# FTDI_Basic-v21-5V.net
KiCad netlist of a schematic drawn in EAGLE
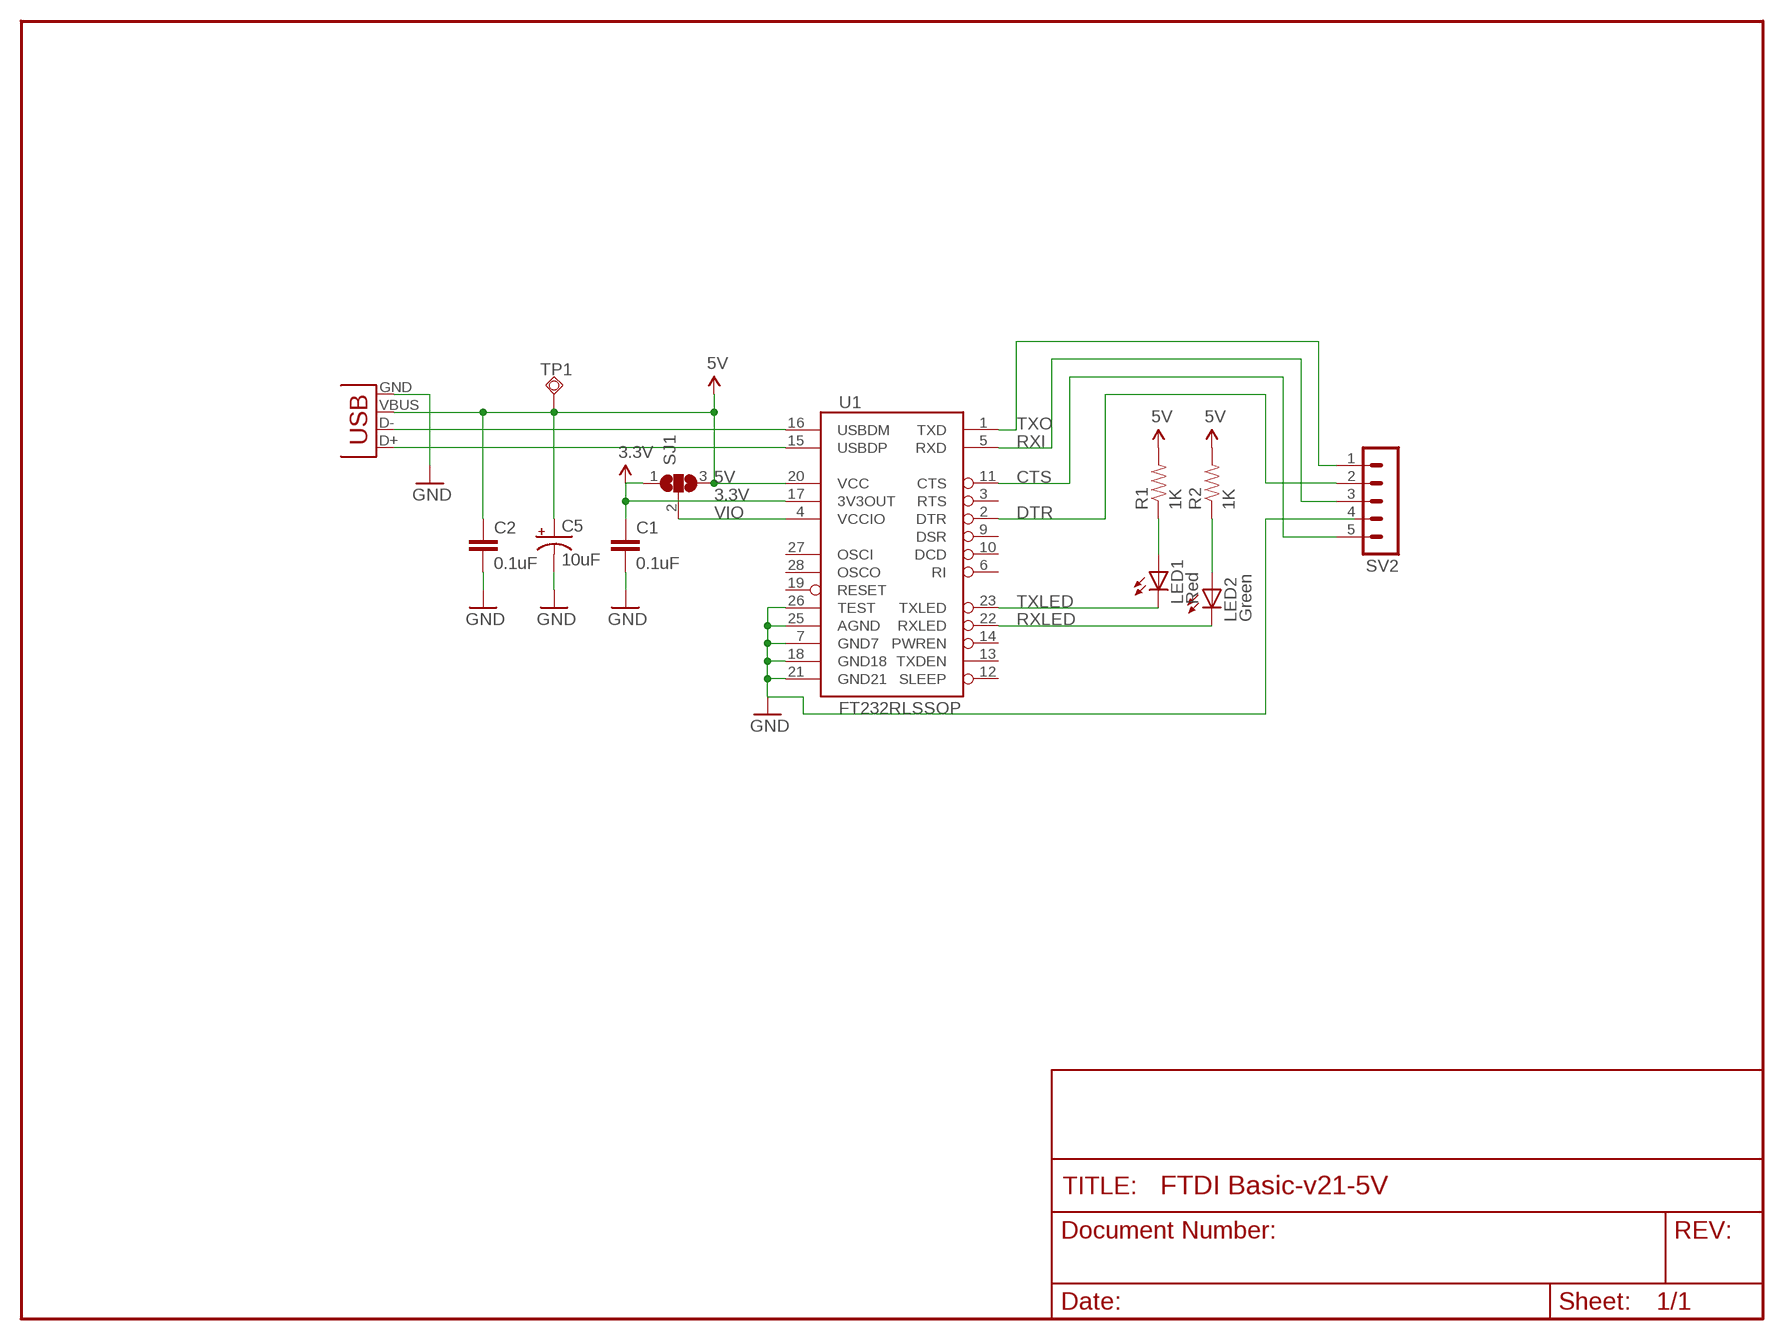
[diagram p0: schematic, sheet 1]

(export (version "E")
  (design (tool "Eeschema 10.0.6"))
  (components
    (comp (ref "C1")
      (value "0.1uF")
      (footprint "eagle-import:0402-CAP")
      (libsource (lib "eagle-import") (part "CAP0402-CAP"))
    )
    (comp (ref "C2")
      (value "0.1uF")
      (footprint "eagle-import:0402-CAP")
      (libsource (lib "eagle-import") (part "CAP0402-CAP"))
    )
    (comp (ref "C5")
      (value "10uF")
      (footprint "eagle-import:EIA3216")
      (libsource (lib "eagle-import") (part "CAP_POL1206"))
    )
    (comp (ref "LED1")
      (value "Red")
      (footprint "eagle-import:LED-0603")
      (libsource (lib "eagle-import") (part "LED0603"))
    )
    (comp (ref "LED2")
      (value "Green")
      (footprint "eagle-import:LED-0603")
      (libsource (lib "eagle-import") (part "LED0603"))
    )
    (comp (ref "R1")
      (value "1K")
      (footprint "eagle-import:0402-RES")
      (libsource (lib "eagle-import") (part "RESISTOR0402-RES"))
    )
    (comp (ref "R2")
      (value "1K")
      (footprint "eagle-import:0402-RES")
      (libsource (lib "eagle-import") (part "RESISTOR0402-RES"))
    )
    (comp (ref "SJ1")
      (value "SJ2W")
      (footprint "eagle-import:SJ_2")
      (libsource (lib "eagle-import") (part "SJ2W"))
    )
    (comp (ref "SV2")
      (value "MA05-1")
      (footprint "eagle-import:MA05-1")
      (libsource (lib "eagle-import") (part "MA05-1"))
    )
    (comp (ref "TP1")
      (value "TPSQPAD1-13")
      (footprint "eagle-import:P1-13")
      (libsource (lib "eagle-import") (part "TPSQPAD1-13"))
    )
    (comp (ref "U1")
      (value "FT232RLSSOP")
      (footprint "eagle-import:SSOP28DB")
      (libsource (lib "eagle-import") (part "FT232RLSSOP"))
    )
    (comp (ref "X2")
      (value "USBPTH")
      (footprint "eagle-import:USB-B-PTH")
      (libsource (lib "eagle-import") (part "USBPTH"))
    )
  )
  (nets
    (net (code "1") (name "/CTS") (class "Default")
      (node (ref "SV2") (pin "5") (pinfunction "5_5") (pintype "passive"))
      (node (ref "U1") (pin "11") (pinfunction "CTS_11") (pintype "input"))
    )
    (net (code "2") (name "/DTR") (class "Default")
      (node (ref "SV2") (pin "2") (pinfunction "2_2") (pintype "passive"))
      (node (ref "U1") (pin "2") (pinfunction "DTR_2") (pintype "output"))
    )
    (net (code "3") (name "/RXI") (class "Default")
      (node (ref "SV2") (pin "3") (pinfunction "3_3") (pintype "passive"))
      (node (ref "U1") (pin "5") (pinfunction "RXD_5") (pintype "input"))
    )
    (net (code "4") (name "/RXLED") (class "Default")
      (node (ref "LED2") (pin "C") (pinfunction "C_C") (pintype "passive"))
      (node (ref "U1") (pin "22") (pinfunction "RXLED_22") (pintype "input"))
    )
    (net (code "5") (name "/TXLED") (class "Default")
      (node (ref "LED1") (pin "C") (pinfunction "C_C") (pintype "passive"))
      (node (ref "U1") (pin "23") (pinfunction "TXLED_23") (pintype "input"))
    )
    (net (code "6") (name "/TXO") (class "Default")
      (node (ref "SV2") (pin "1") (pinfunction "1_1") (pintype "passive"))
      (node (ref "U1") (pin "1") (pinfunction "TXD_1") (pintype "output"))
    )
    (net (code "7") (name "/VIO") (class "Default")
      (node (ref "SJ1") (pin "2") (pinfunction "2_2") (pintype "passive"))
      (node (ref "U1") (pin "4") (pinfunction "VCCIO_4") (pintype "power_in"))
    )
    (net (code "8") (name "3.3V") (class "Default")
      (node (ref "C1") (pin "1") (pinfunction "1_1") (pintype "passive"))
      (node (ref "SJ1") (pin "1") (pinfunction "1_1") (pintype "passive"))
      (node (ref "U1") (pin "17") (pinfunction "3V3OUT_17") (pintype "output"))
    )
    (net (code "9") (name "5V") (class "Default")
      (node (ref "C2") (pin "1") (pinfunction "1_1") (pintype "passive"))
      (node (ref "C5") (pin "A") (pinfunction "+_A") (pintype "passive"))
      (node (ref "R1") (pin "2") (pinfunction "2_2") (pintype "passive"))
      (node (ref "R2") (pin "2") (pinfunction "2_2") (pintype "passive"))
      (node (ref "SJ1") (pin "3") (pinfunction "3_3") (pintype "passive"))
      (node (ref "TP1") (pin "TP") (pinfunction "TP_TP") (pintype "input"))
      (node (ref "U1") (pin "20") (pinfunction "VCC_20") (pintype "power_in"))
      (node (ref "X2") (pin "VBUS") (pinfunction "VBUS_VBUS") (pintype "bidirectional"))
    )
    (net (code "10") (name "GND") (class "Default")
      (node (ref "C1") (pin "2") (pinfunction "2_2") (pintype "passive"))
      (node (ref "C2") (pin "2") (pinfunction "2_2") (pintype "passive"))
      (node (ref "C5") (pin "C") (pinfunction "-_C") (pintype "passive"))
      (node (ref "SV2") (pin "4") (pinfunction "4_4") (pintype "passive"))
      (node (ref "U1") (pin "18") (pinfunction "GND18_18") (pintype "power_in"))
      (node (ref "U1") (pin "21") (pinfunction "GND21_21") (pintype "power_in"))
      (node (ref "U1") (pin "25") (pinfunction "AGND_25") (pintype "power_in"))
      (node (ref "U1") (pin "26") (pinfunction "TEST_26") (pintype "input"))
      (node (ref "U1") (pin "7") (pinfunction "GND7_7") (pintype "power_in"))
      (node (ref "X2") (pin "GND") (pinfunction "GND_GND") (pintype "bidirectional"))
    )
    (net (code "11") (name "Net-(LED1-PadA)") (class "Default")
      (node (ref "LED1") (pin "A") (pinfunction "A_A") (pintype "passive"))
      (node (ref "R1") (pin "1") (pinfunction "1_1") (pintype "passive"))
    )
    (net (code "12") (name "Net-(LED2-PadA)") (class "Default")
      (node (ref "LED2") (pin "A") (pinfunction "A_A") (pintype "passive"))
      (node (ref "R2") (pin "1") (pinfunction "1_1") (pintype "passive"))
    )
    (net (code "13") (name "Net-(U1-USBDM)") (class "Default")
      (node (ref "U1") (pin "16") (pinfunction "USBDM_16") (pintype "bidirectional"))
      (node (ref "X2") (pin "D-") (pinfunction "D-_D-") (pintype "bidirectional"))
    )
    (net (code "14") (name "Net-(U1-USBDP)") (class "Default")
      (node (ref "U1") (pin "15") (pinfunction "USBDP_15") (pintype "bidirectional"))
      (node (ref "X2") (pin "D+") (pinfunction "D+_D+") (pintype "bidirectional"))
    )
    (net (code "15") (name "unconnected-(U1-DCD-Pad10)") (class "Default")
      (node (ref "U1") (pin "10") (pinfunction "DCD_10") (pintype "input"))
    )
    (net (code "16") (name "unconnected-(U1-DSR-Pad9)") (class "Default")
      (node (ref "U1") (pin "9") (pinfunction "DSR_9") (pintype "input"))
    )
    (net (code "17") (name "unconnected-(U1-OSCI-Pad27)") (class "Default")
      (node (ref "U1") (pin "27") (pinfunction "OSCI_27") (pintype "input"))
    )
    (net (code "18") (name "unconnected-(U1-OSCO-Pad28)") (class "Default")
      (node (ref "U1") (pin "28") (pinfunction "OSCO_28") (pintype "output"))
    )
    (net (code "19") (name "unconnected-(U1-PWREN-Pad14)") (class "Default")
      (node (ref "U1") (pin "14") (pinfunction "PWREN_14") (pintype "input"))
    )
    (net (code "20") (name "unconnected-(U1-RESET-Pad19)") (class "Default")
      (node (ref "U1") (pin "19") (pinfunction "RESET_19") (pintype "input"))
    )
    (net (code "21") (name "unconnected-(U1-RI-Pad6)") (class "Default")
      (node (ref "U1") (pin "6") (pinfunction "RI_6") (pintype "input"))
    )
    (net (code "22") (name "unconnected-(U1-RTS-Pad3)") (class "Default")
      (node (ref "U1") (pin "3") (pinfunction "RTS_3") (pintype "output"))
    )
    (net (code "23") (name "unconnected-(U1-SLEEP-Pad12)") (class "Default")
      (node (ref "U1") (pin "12") (pinfunction "SLEEP_12") (pintype "input"))
    )
    (net (code "24") (name "unconnected-(U1-TXDEN-Pad13)") (class "Default")
      (node (ref "U1") (pin "13") (pinfunction "TXDEN_13") (pintype "input"))
    )
  )
)
